# COM_R_BOARD.net
KiCad netlist of a schematic drawn in EAGLE
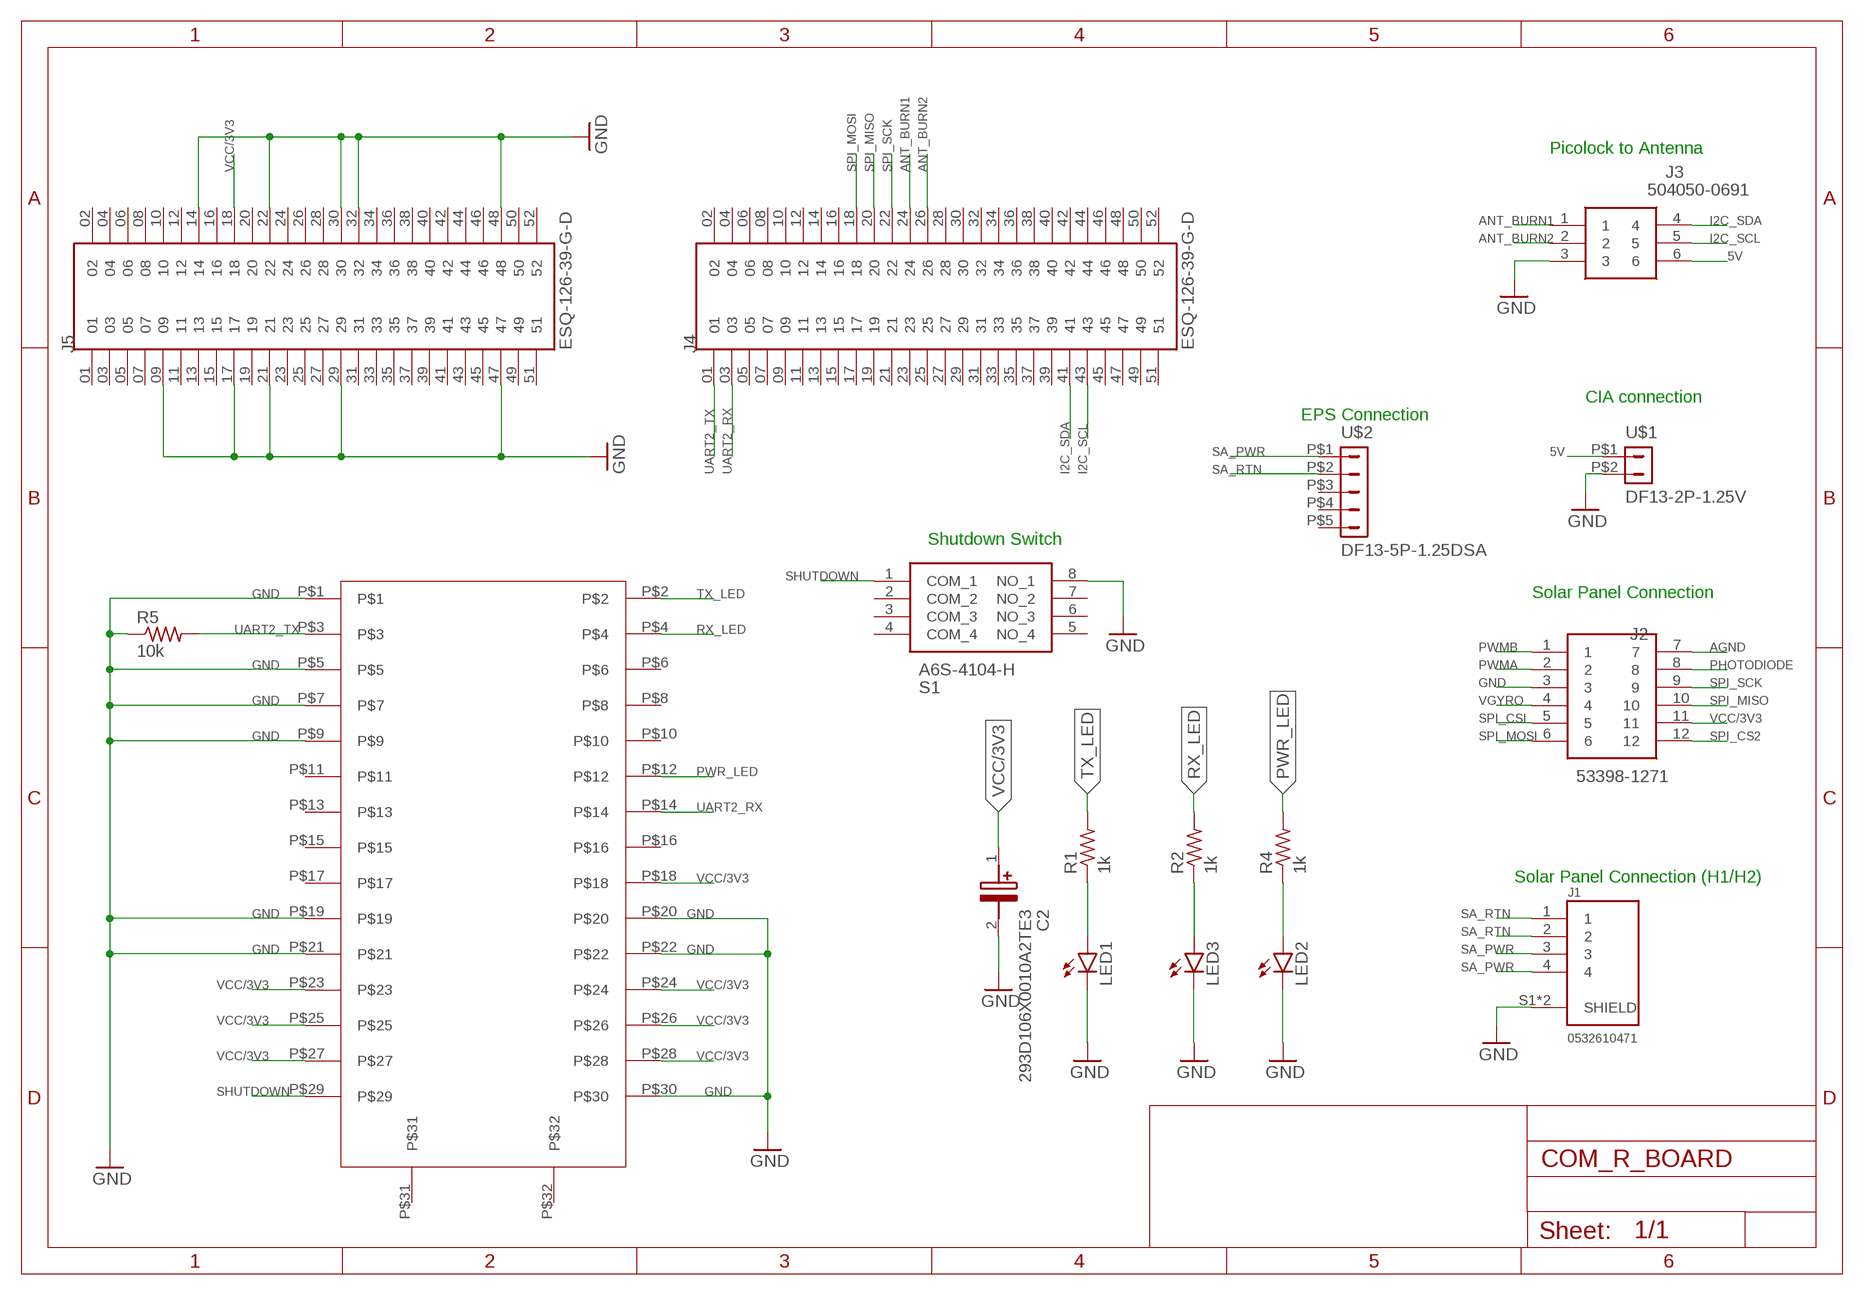
[diagram p0: schematic, sheet 1]

(export (version "E")
  (design (tool "Eeschema 10.0.6"))
  (components
    (comp (ref "C2")
      (value "293D106X0010A2TE3")
      (footprint "eagle-import:CAPPM3216X180N")
      (fields (field (name "MOUSER_PART_NUMBER") "74-293D106X0010A2TE3"))
      (libsource (lib "eagle-import") (part "293D106X0010A2TE3"))
    )
    (comp (ref "J1")
      (value "0532610471")
      (footprint "eagle-import:MOLEX_0532610471")
      (fields (field (name "MF") "Molex"))
      (libsource (lib "eagle-import") (part "0532610471"))
    )
    (comp (ref "J2")
      (value "53398-1271")
      (footprint "eagle-import:53398-1271")
      (fields (field (name "MOUSER_PART_NUMBER") "538-53398-1271"))
      (libsource (lib "eagle-import") (part "53398-1271"))
    )
    (comp (ref "J3")
      (value "504050-0691")
      (footprint "eagle-import:504050-0691_2")
      (fields (field (name "MOUSER_PART_NUMBER") "538-504050-0691"))
      (libsource (lib "eagle-import") (part "504050-0691"))
    )
    (comp (ref "J4")
      (value "ESQ-126-39-G-D")
      (footprint "eagle-import:SAMTEC_ESQ-126-39-G-D")
      (fields (field (name "MF") "Samtec"))
      (libsource (lib "eagle-import") (part "ESQ-126-39-G-D"))
    )
    (comp (ref "J5")
      (value "ESQ-126-39-G-D")
      (footprint "eagle-import:SAMTEC_ESQ-126-39-G-D")
      (fields (field (name "MF") "Samtec"))
      (libsource (lib "eagle-import") (part "ESQ-126-39-G-D"))
    )
    (comp (ref "LED1")
      (value "LEDCHIP-LED0805")
      (footprint "eagle-import:CHIP-LED0805")
      (libsource (lib "eagle-import") (part "LEDCHIP-LED0805"))
    )
    (comp (ref "LED2")
      (value "LEDCHIP-LED0805")
      (footprint "eagle-import:CHIP-LED0805")
      (libsource (lib "eagle-import") (part "LEDCHIP-LED0805"))
    )
    (comp (ref "LED3")
      (value "LEDCHIP-LED0805")
      (footprint "eagle-import:CHIP-LED0805")
      (libsource (lib "eagle-import") (part "LEDCHIP-LED0805"))
    )
    (comp (ref "R1")
      (value "1k")
      (footprint "eagle-import:M0805")
      (libsource (lib "eagle-import") (part "R-US_M0805"))
    )
    (comp (ref "R2")
      (value "1k")
      (footprint "eagle-import:M0805")
      (libsource (lib "eagle-import") (part "R-US_M0805"))
    )
    (comp (ref "R4")
      (value "1k")
      (footprint "eagle-import:M0805")
      (libsource (lib "eagle-import") (part "R-US_M0805"))
    )
    (comp (ref "R5")
      (value "10k")
      (footprint "eagle-import:WSC01_2")
      (libsource (lib "eagle-import") (part "R-US_WSC01/2"))
    )
    (comp (ref "S1")
      (value "A6S-4104-H")
      (footprint "eagle-import:A6S4104H")
      (fields (field (name "MOUSER_PART_NUMBER") "653-A6S-4104-H"))
      (libsource (lib "eagle-import") (part "A6S-4104-H"))
    )
    (comp (ref "U$1")
      (value "DF13-2P-1.25V")
      (footprint "eagle-import:DF13C-2P-1.25V")
      (libsource (lib "eagle-import") (part "DF13-2P-1.25V"))
    )
    (comp (ref "U$2")
      (value "DF13-5P-1.25DSA")
      (footprint "eagle-import:DF13-5P-1.25DSA")
      (libsource (lib "eagle-import") (part "DF13-5P-1.25DSA"))
    )
    (comp (ref "U$3")
      (value "KYOCERA_5046_30PIN")
      (footprint "eagle-import:KYOCERA_5046_30PIN")
      (libsource (lib "eagle-import") (part "KYOCERA_5046_30PIN"))
    )
  )
  (nets
    (net (code "1") (name "/5V") (class "Default")
      (node (ref "J3") (pin "6") (pinfunction "6_6") (pintype "bidirectional"))
      (node (ref "U$1") (pin "P$1") (pinfunction "1_P$1") (pintype "passive"))
    )
    (net (code "2") (name "/AGND") (class "Default")
      (node (ref "J2") (pin "7") (pinfunction "7_7") (pintype "bidirectional"))
    )
    (net (code "3") (name "/ANT_BURN1") (class "Default")
      (node (ref "J3") (pin "1") (pinfunction "1_1") (pintype "bidirectional"))
      (node (ref "J4") (pin "24") (pinfunction "24_24") (pintype "passive"))
    )
    (net (code "4") (name "/ANT_BURN2") (class "Default")
      (node (ref "J3") (pin "2") (pinfunction "2_2") (pintype "bidirectional"))
      (node (ref "J4") (pin "26") (pinfunction "26_26") (pintype "passive"))
    )
    (net (code "5") (name "/I2C_SCL") (class "Default")
      (node (ref "J3") (pin "5") (pinfunction "5_5") (pintype "bidirectional"))
      (node (ref "J4") (pin "43") (pinfunction "43_43") (pintype "passive"))
    )
    (net (code "6") (name "/I2C_SDA") (class "Default")
      (node (ref "J3") (pin "4") (pinfunction "4_4") (pintype "bidirectional"))
      (node (ref "J4") (pin "41") (pinfunction "41_41") (pintype "passive"))
    )
    (net (code "7") (name "/PHOTODIODE") (class "Default")
      (node (ref "J2") (pin "8") (pinfunction "8_8") (pintype "bidirectional"))
    )
    (net (code "8") (name "/PWMA") (class "Default")
      (node (ref "J2") (pin "2") (pinfunction "2_2") (pintype "bidirectional"))
    )
    (net (code "9") (name "/PWMB") (class "Default")
      (node (ref "J2") (pin "1") (pinfunction "1_1") (pintype "bidirectional"))
    )
    (net (code "10") (name "/SA_PWR") (class "Default")
      (node (ref "J1") (pin "3") (pinfunction "3_3") (pintype "passive"))
      (node (ref "J1") (pin "4") (pinfunction "4_4") (pintype "passive"))
      (node (ref "U$2") (pin "P$1") (pinfunction "1_P$1") (pintype "passive"))
    )
    (net (code "11") (name "/SA_RTN") (class "Default")
      (node (ref "J1") (pin "1") (pinfunction "1_1") (pintype "passive"))
      (node (ref "J1") (pin "2") (pinfunction "2_2") (pintype "passive"))
      (node (ref "U$2") (pin "P$2") (pinfunction "2_P$2") (pintype "passive"))
    )
    (net (code "12") (name "/SHUTDOWN") (class "Default")
      (node (ref "S1") (pin "1") (pinfunction "COM_1_1") (pintype "bidirectional"))
      (node (ref "U$3") (pin "P$29") (pinfunction "P$29_P$29") (pintype "bidirectional"))
    )
    (net (code "13") (name "/SPI_CS2") (class "Default")
      (node (ref "J2") (pin "12") (pinfunction "12_12") (pintype "bidirectional"))
    )
    (net (code "14") (name "/SPI_CSI") (class "Default")
      (node (ref "J2") (pin "5") (pinfunction "5_5") (pintype "bidirectional"))
    )
    (net (code "15") (name "/SPI_MISO") (class "Default")
      (node (ref "J2") (pin "10") (pinfunction "10_10") (pintype "bidirectional"))
      (node (ref "J4") (pin "20") (pinfunction "20_20") (pintype "passive"))
    )
    (net (code "16") (name "/SPI_MOSI") (class "Default")
      (node (ref "J2") (pin "6") (pinfunction "6_6") (pintype "bidirectional"))
      (node (ref "J4") (pin "18") (pinfunction "18_18") (pintype "passive"))
    )
    (net (code "17") (name "/SPI_SCK") (class "Default")
      (node (ref "J2") (pin "9") (pinfunction "9_9") (pintype "bidirectional"))
      (node (ref "J4") (pin "22") (pinfunction "22_22") (pintype "passive"))
    )
    (net (code "18") (name "/UART2_RX") (class "Default")
      (node (ref "J4") (pin "03") (pinfunction "03_03") (pintype "passive"))
      (node (ref "U$3") (pin "P$14") (pinfunction "P$14_P$14") (pintype "bidirectional"))
    )
    (net (code "19") (name "/UART2_TX") (class "Default")
      (node (ref "J4") (pin "01") (pinfunction "01_01") (pintype "passive"))
      (node (ref "R5") (pin "2") (pinfunction "2_2") (pintype "passive"))
      (node (ref "U$3") (pin "P$3") (pinfunction "P$3_P$3") (pintype "bidirectional"))
    )
    (net (code "20") (name "/VGYRO") (class "Default")
      (node (ref "J2") (pin "4") (pinfunction "4_4") (pintype "bidirectional"))
    )
    (net (code "21") (name "GND") (class "Default")
      (node (ref "C2") (pin "2") (pinfunction "-_2") (pintype "bidirectional"))
      (node (ref "J1") (pin "S1") (pinfunction "SHIELD_S1") (pintype "passive"))
      (node (ref "J1") (pin "S2") (pinfunction "SHIELD_S2") (pintype "passive"))
      (node (ref "J2") (pin "3") (pinfunction "3_3") (pintype "bidirectional"))
      (node (ref "J3") (pin "3") (pinfunction "3_3") (pintype "bidirectional"))
      (node (ref "J5") (pin "09") (pinfunction "09_09") (pintype "passive"))
      (node (ref "J5") (pin "14") (pinfunction "14_14") (pintype "passive"))
      (node (ref "J5") (pin "17") (pinfunction "17_17") (pintype "passive"))
      (node (ref "J5") (pin "21") (pinfunction "21_21") (pintype "passive"))
      (node (ref "J5") (pin "22") (pinfunction "22_22") (pintype "passive"))
      (node (ref "J5") (pin "29") (pinfunction "29_29") (pintype "passive"))
      (node (ref "J5") (pin "30") (pinfunction "30_30") (pintype "passive"))
      (node (ref "J5") (pin "32") (pinfunction "32_32") (pintype "passive"))
      (node (ref "J5") (pin "47") (pinfunction "47_47") (pintype "passive"))
      (node (ref "J5") (pin "48") (pinfunction "48_48") (pintype "passive"))
      (node (ref "LED1") (pin "C") (pinfunction "C_C") (pintype "passive"))
      (node (ref "LED2") (pin "C") (pinfunction "C_C") (pintype "passive"))
      (node (ref "LED3") (pin "C") (pinfunction "C_C") (pintype "passive"))
      (node (ref "R5") (pin "1") (pinfunction "1_1") (pintype "passive"))
      (node (ref "S1") (pin "8") (pinfunction "NO_1_8") (pintype "bidirectional"))
      (node (ref "U$1") (pin "P$2") (pinfunction "2_P$2") (pintype "passive"))
      (node (ref "U$3") (pin "P$1") (pinfunction "P$1_P$1") (pintype "bidirectional"))
      (node (ref "U$3") (pin "P$19") (pinfunction "P$19_P$19") (pintype "bidirectional"))
      (node (ref "U$3") (pin "P$20") (pinfunction "P$20_P$20") (pintype "bidirectional"))
      (node (ref "U$3") (pin "P$21") (pinfunction "P$21_P$21") (pintype "bidirectional"))
      (node (ref "U$3") (pin "P$22") (pinfunction "P$22_P$22") (pintype "bidirectional"))
      (node (ref "U$3") (pin "P$30") (pinfunction "P$30_P$30") (pintype "bidirectional"))
      (node (ref "U$3") (pin "P$5") (pinfunction "P$5_P$5") (pintype "bidirectional"))
      (node (ref "U$3") (pin "P$7") (pinfunction "P$7_P$7") (pintype "bidirectional"))
      (node (ref "U$3") (pin "P$9") (pinfunction "P$9_P$9") (pintype "bidirectional"))
    )
    (net (code "22") (name "Net-(LED1-PadA)") (class "Default")
      (node (ref "LED1") (pin "A") (pinfunction "A_A") (pintype "passive"))
      (node (ref "R1") (pin "1") (pinfunction "1_1") (pintype "passive"))
    )
    (net (code "23") (name "Net-(LED2-PadA)") (class "Default")
      (node (ref "LED2") (pin "A") (pinfunction "A_A") (pintype "passive"))
      (node (ref "R4") (pin "1") (pinfunction "1_1") (pintype "passive"))
    )
    (net (code "24") (name "Net-(LED3-PadA)") (class "Default")
      (node (ref "LED3") (pin "A") (pinfunction "A_A") (pintype "passive"))
      (node (ref "R2") (pin "1") (pinfunction "1_1") (pintype "passive"))
    )
    (net (code "25") (name "PWR_LED") (class "Default")
      (node (ref "R4") (pin "2") (pinfunction "2_2") (pintype "passive"))
      (node (ref "U$3") (pin "P$12") (pinfunction "P$12_P$12") (pintype "bidirectional"))
    )
    (net (code "26") (name "RX_LED") (class "Default")
      (node (ref "R2") (pin "2") (pinfunction "2_2") (pintype "passive"))
      (node (ref "U$3") (pin "P$4") (pinfunction "P$4_P$4") (pintype "bidirectional"))
    )
    (net (code "27") (name "TX_LED") (class "Default")
      (node (ref "R1") (pin "2") (pinfunction "2_2") (pintype "passive"))
      (node (ref "U$3") (pin "P$2") (pinfunction "P$2_P$2") (pintype "bidirectional"))
    )
    (net (code "28") (name "VCC{slash}3V3") (class "Default")
      (node (ref "C2") (pin "1") (pinfunction "+_1") (pintype "bidirectional"))
      (node (ref "J2") (pin "11") (pinfunction "11_11") (pintype "bidirectional"))
      (node (ref "J5") (pin "18") (pinfunction "18_18") (pintype "passive"))
      (node (ref "U$3") (pin "P$18") (pinfunction "P$18_P$18") (pintype "bidirectional"))
      (node (ref "U$3") (pin "P$23") (pinfunction "P$23_P$23") (pintype "bidirectional"))
      (node (ref "U$3") (pin "P$24") (pinfunction "P$24_P$24") (pintype "bidirectional"))
      (node (ref "U$3") (pin "P$25") (pinfunction "P$25_P$25") (pintype "bidirectional"))
      (node (ref "U$3") (pin "P$26") (pinfunction "P$26_P$26") (pintype "bidirectional"))
      (node (ref "U$3") (pin "P$27") (pinfunction "P$27_P$27") (pintype "bidirectional"))
      (node (ref "U$3") (pin "P$28") (pinfunction "P$28_P$28") (pintype "bidirectional"))
    )
    (net (code "29") (name "unconnected-(J4-Pad02)") (class "Default")
      (node (ref "J4") (pin "02") (pinfunction "02_02") (pintype "passive"))
    )
    (net (code "30") (name "unconnected-(J4-Pad04)") (class "Default")
      (node (ref "J4") (pin "04") (pinfunction "04_04") (pintype "passive"))
    )
    (net (code "31") (name "unconnected-(J4-Pad05)") (class "Default")
      (node (ref "J4") (pin "05") (pinfunction "05_05") (pintype "passive"))
    )
    (net (code "32") (name "unconnected-(J4-Pad06)") (class "Default")
      (node (ref "J4") (pin "06") (pinfunction "06_06") (pintype "passive"))
    )
    (net (code "33") (name "unconnected-(J4-Pad07)") (class "Default")
      (node (ref "J4") (pin "07") (pinfunction "07_07") (pintype "passive"))
    )
    (net (code "34") (name "unconnected-(J4-Pad08)") (class "Default")
      (node (ref "J4") (pin "08") (pinfunction "08_08") (pintype "passive"))
    )
    (net (code "35") (name "unconnected-(J4-Pad09)") (class "Default")
      (node (ref "J4") (pin "09") (pinfunction "09_09") (pintype "passive"))
    )
    (net (code "36") (name "unconnected-(J4-Pad10)") (class "Default")
      (node (ref "J4") (pin "10") (pinfunction "10_10") (pintype "passive"))
    )
    (net (code "37") (name "unconnected-(J4-Pad11)") (class "Default")
      (node (ref "J4") (pin "11") (pinfunction "11_11") (pintype "passive"))
    )
    (net (code "38") (name "unconnected-(J4-Pad12)") (class "Default")
      (node (ref "J4") (pin "12") (pinfunction "12_12") (pintype "passive"))
    )
    (net (code "39") (name "unconnected-(J4-Pad13)") (class "Default")
      (node (ref "J4") (pin "13") (pinfunction "13_13") (pintype "passive"))
    )
    (net (code "40") (name "unconnected-(J4-Pad14)") (class "Default")
      (node (ref "J4") (pin "14") (pinfunction "14_14") (pintype "passive"))
    )
    (net (code "41") (name "unconnected-(J4-Pad15)") (class "Default")
      (node (ref "J4") (pin "15") (pinfunction "15_15") (pintype "passive"))
    )
    (net (code "42") (name "unconnected-(J4-Pad16)") (class "Default")
      (node (ref "J4") (pin "16") (pinfunction "16_16") (pintype "passive"))
    )
    (net (code "43") (name "unconnected-(J4-Pad17)") (class "Default")
      (node (ref "J4") (pin "17") (pinfunction "17_17") (pintype "passive"))
    )
    (net (code "44") (name "unconnected-(J4-Pad19)") (class "Default")
      (node (ref "J4") (pin "19") (pinfunction "19_19") (pintype "passive"))
    )
    (net (code "45") (name "unconnected-(J4-Pad21)") (class "Default")
      (node (ref "J4") (pin "21") (pinfunction "21_21") (pintype "passive"))
    )
    (net (code "46") (name "unconnected-(J4-Pad23)") (class "Default")
      (node (ref "J4") (pin "23") (pinfunction "23_23") (pintype "passive"))
    )
    (net (code "47") (name "unconnected-(J4-Pad25)") (class "Default")
      (node (ref "J4") (pin "25") (pinfunction "25_25") (pintype "passive"))
    )
    (net (code "48") (name "unconnected-(J4-Pad27)") (class "Default")
      (node (ref "J4") (pin "27") (pinfunction "27_27") (pintype "passive"))
    )
    (net (code "49") (name "unconnected-(J4-Pad28)") (class "Default")
      (node (ref "J4") (pin "28") (pinfunction "28_28") (pintype "passive"))
    )
    (net (code "50") (name "unconnected-(J4-Pad29)") (class "Default")
      (node (ref "J4") (pin "29") (pinfunction "29_29") (pintype "passive"))
    )
    (net (code "51") (name "unconnected-(J4-Pad30)") (class "Default")
      (node (ref "J4") (pin "30") (pinfunction "30_30") (pintype "passive"))
    )
    (net (code "52") (name "unconnected-(J4-Pad31)") (class "Default")
      (node (ref "J4") (pin "31") (pinfunction "31_31") (pintype "passive"))
    )
    (net (code "53") (name "unconnected-(J4-Pad32)") (class "Default")
      (node (ref "J4") (pin "32") (pinfunction "32_32") (pintype "passive"))
    )
    (net (code "54") (name "unconnected-(J4-Pad33)") (class "Default")
      (node (ref "J4") (pin "33") (pinfunction "33_33") (pintype "passive"))
    )
    (net (code "55") (name "unconnected-(J4-Pad34)") (class "Default")
      (node (ref "J4") (pin "34") (pinfunction "34_34") (pintype "passive"))
    )
    (net (code "56") (name "unconnected-(J4-Pad35)") (class "Default")
      (node (ref "J4") (pin "35") (pinfunction "35_35") (pintype "passive"))
    )
    (net (code "57") (name "unconnected-(J4-Pad36)") (class "Default")
      (node (ref "J4") (pin "36") (pinfunction "36_36") (pintype "passive"))
    )
    (net (code "58") (name "unconnected-(J4-Pad37)") (class "Default")
      (node (ref "J4") (pin "37") (pinfunction "37_37") (pintype "passive"))
    )
    (net (code "59") (name "unconnected-(J4-Pad38)") (class "Default")
      (node (ref "J4") (pin "38") (pinfunction "38_38") (pintype "passive"))
    )
    (net (code "60") (name "unconnected-(J4-Pad39)") (class "Default")
      (node (ref "J4") (pin "39") (pinfunction "39_39") (pintype "passive"))
    )
    (net (code "61") (name "unconnected-(J4-Pad40)") (class "Default")
      (node (ref "J4") (pin "40") (pinfunction "40_40") (pintype "passive"))
    )
    (net (code "62") (name "unconnected-(J4-Pad42)") (class "Default")
      (node (ref "J4") (pin "42") (pinfunction "42_42") (pintype "passive"))
    )
    (net (code "63") (name "unconnected-(J4-Pad44)") (class "Default")
      (node (ref "J4") (pin "44") (pinfunction "44_44") (pintype "passive"))
    )
    (net (code "64") (name "unconnected-(J4-Pad45)") (class "Default")
      (node (ref "J4") (pin "45") (pinfunction "45_45") (pintype "passive"))
    )
    (net (code "65") (name "unconnected-(J4-Pad46)") (class "Default")
      (node (ref "J4") (pin "46") (pinfunction "46_46") (pintype "passive"))
    )
    (net (code "66") (name "unconnected-(J4-Pad47)") (class "Default")
      (node (ref "J4") (pin "47") (pinfunction "47_47") (pintype "passive"))
    )
    (net (code "67") (name "unconnected-(J4-Pad48)") (class "Default")
      (node (ref "J4") (pin "48") (pinfunction "48_48") (pintype "passive"))
    )
    (net (code "68") (name "unconnected-(J4-Pad49)") (class "Default")
      (node (ref "J4") (pin "49") (pinfunction "49_49") (pintype "passive"))
    )
    (net (code "69") (name "unconnected-(J4-Pad50)") (class "Default")
      (node (ref "J4") (pin "50") (pinfunction "50_50") (pintype "passive"))
    )
    (net (code "70") (name "unconnected-(J4-Pad51)") (class "Default")
      (node (ref "J4") (pin "51") (pinfunction "51_51") (pintype "passive"))
    )
    (net (code "71") (name "unconnected-(J4-Pad52)") (class "Default")
      (node (ref "J4") (pin "52") (pinfunction "52_52") (pintype "passive"))
    )
    (net (code "72") (name "unconnected-(J5-Pad01)") (class "Default")
      (node (ref "J5") (pin "01") (pinfunction "01_01") (pintype "passive"))
    )
    (net (code "73") (name "unconnected-(J5-Pad02)") (class "Default")
      (node (ref "J5") (pin "02") (pinfunction "02_02") (pintype "passive"))
    )
    (net (code "74") (name "unconnected-(J5-Pad03)") (class "Default")
      (node (ref "J5") (pin "03") (pinfunction "03_03") (pintype "passive"))
    )
    (net (code "75") (name "unconnected-(J5-Pad04)") (class "Default")
      (node (ref "J5") (pin "04") (pinfunction "04_04") (pintype "passive"))
    )
    (net (code "76") (name "unconnected-(J5-Pad05)") (class "Default")
      (node (ref "J5") (pin "05") (pinfunction "05_05") (pintype "passive"))
    )
    (net (code "77") (name "unconnected-(J5-Pad06)") (class "Default")
      (node (ref "J5") (pin "06") (pinfunction "06_06") (pintype "passive"))
    )
    (net (code "78") (name "unconnected-(J5-Pad07)") (class "Default")
      (node (ref "J5") (pin "07") (pinfunction "07_07") (pintype "passive"))
    )
    (net (code "79") (name "unconnected-(J5-Pad08)") (class "Default")
      (node (ref "J5") (pin "08") (pinfunction "08_08") (pintype "passive"))
    )
    (net (code "80") (name "unconnected-(J5-Pad10)") (class "Default")
      (node (ref "J5") (pin "10") (pinfunction "10_10") (pintype "passive"))
    )
    (net (code "81") (name "unconnected-(J5-Pad11)") (class "Default")
      (node (ref "J5") (pin "11") (pinfunction "11_11") (pintype "passive"))
    )
    (net (code "82") (name "unconnected-(J5-Pad12)") (class "Default")
      (node (ref "J5") (pin "12") (pinfunction "12_12") (pintype "passive"))
    )
    (net (code "83") (name "unconnected-(J5-Pad13)") (class "Default")
      (node (ref "J5") (pin "13") (pinfunction "13_13") (pintype "passive"))
    )
    (net (code "84") (name "unconnected-(J5-Pad15)") (class "Default")
      (node (ref "J5") (pin "15") (pinfunction "15_15") (pintype "passive"))
    )
    (net (code "85") (name "unconnected-(J5-Pad16)") (class "Default")
      (node (ref "J5") (pin "16") (pinfunction "16_16") (pintype "passive"))
    )
    (net (code "86") (name "unconnected-(J5-Pad19)") (class "Default")
      (node (ref "J5") (pin "19") (pinfunction "19_19") (pintype "passive"))
    )
    (net (code "87") (name "unconnected-(J5-Pad20)") (class "Default")
      (node (ref "J5") (pin "20") (pinfunction "20_20") (pintype "passive"))
    )
    (net (code "88") (name "unconnected-(J5-Pad23)") (class "Default")
      (node (ref "J5") (pin "23") (pinfunction "23_23") (pintype "passive"))
    )
    (net (code "89") (name "unconnected-(J5-Pad24)") (class "Default")
      (node (ref "J5") (pin "24") (pinfunction "24_24") (pintype "passive"))
    )
    (net (code "90") (name "unconnected-(J5-Pad25)") (class "Default")
      (node (ref "J5") (pin "25") (pinfunction "25_25") (pintype "passive"))
    )
    (net (code "91") (name "unconnected-(J5-Pad26)") (class "Default")
      (node (ref "J5") (pin "26") (pinfunction "26_26") (pintype "passive"))
    )
    (net (code "92") (name "unconnected-(J5-Pad27)") (class "Default")
      (node (ref "J5") (pin "27") (pinfunction "27_27") (pintype "passive"))
    )
    (net (code "93") (name "unconnected-(J5-Pad28)") (class "Default")
      (node (ref "J5") (pin "28") (pinfunction "28_28") (pintype "passive"))
    )
    (net (code "94") (name "unconnected-(J5-Pad31)") (class "Default")
      (node (ref "J5") (pin "31") (pinfunction "31_31") (pintype "passive"))
    )
    (net (code "95") (name "unconnected-(J5-Pad33)") (class "Default")
      (node (ref "J5") (pin "33") (pinfunction "33_33") (pintype "passive"))
    )
    (net (code "96") (name "unconnected-(J5-Pad34)") (class "Default")
      (node (ref "J5") (pin "34") (pinfunction "34_34") (pintype "passive"))
    )
    (net (code "97") (name "unconnected-(J5-Pad35)") (class "Default")
      (node (ref "J5") (pin "35") (pinfunction "35_35") (pintype "passive"))
    )
    (net (code "98") (name "unconnected-(J5-Pad36)") (class "Default")
      (node (ref "J5") (pin "36") (pinfunction "36_36") (pintype "passive"))
    )
    (net (code "99") (name "unconnected-(J5-Pad37)") (class "Default")
      (node (ref "J5") (pin "37") (pinfunction "37_37") (pintype "passive"))
    )
    (net (code "100") (name "unconnected-(J5-Pad38)") (class "Default")
      (node (ref "J5") (pin "38") (pinfunction "38_38") (pintype "passive"))
    )
    (net (code "101") (name "unconnected-(J5-Pad39)") (class "Default")
      (node (ref "J5") (pin "39") (pinfunction "39_39") (pintype "passive"))
    )
    (net (code "102") (name "unconnected-(J5-Pad40)") (class "Default")
      (node (ref "J5") (pin "40") (pinfunction "40_40") (pintype "passive"))
    )
    (net (code "103") (name "unconnected-(J5-Pad41)") (class "Default")
      (node (ref "J5") (pin "41") (pinfunction "41_41") (pintype "passive"))
    )
    (net (code "104") (name "unconnected-(J5-Pad42)") (class "Default")
      (node (ref "J5") (pin "42") (pinfunction "42_42") (pintype "passive"))
    )
    (net (code "105") (name "unconnected-(J5-Pad43)") (class "Default")
      (node (ref "J5") (pin "43") (pinfunction "43_43") (pintype "passive"))
    )
    (net (code "106") (name "unconnected-(J5-Pad44)") (class "Default")
      (node (ref "J5") (pin "44") (pinfunction "44_44") (pintype "passive"))
    )
    (net (code "107") (name "unconnected-(J5-Pad45)") (class "Default")
      (node (ref "J5") (pin "45") (pinfunction "45_45") (pintype "passive"))
    )
    (net (code "108") (name "unconnected-(J5-Pad46)") (class "Default")
      (node (ref "J5") (pin "46") (pinfunction "46_46") (pintype "passive"))
    )
    (net (code "109") (name "unconnected-(J5-Pad49)") (class "Default")
      (node (ref "J5") (pin "49") (pinfunction "49_49") (pintype "passive"))
    )
    (net (code "110") (name "unconnected-(J5-Pad50)") (class "Default")
      (node (ref "J5") (pin "50") (pinfunction "50_50") (pintype "passive"))
    )
    (net (code "111") (name "unconnected-(J5-Pad51)") (class "Default")
      (node (ref "J5") (pin "51") (pinfunction "51_51") (pintype "passive"))
    )
    (net (code "112") (name "unconnected-(J5-Pad52)") (class "Default")
      (node (ref "J5") (pin "52") (pinfunction "52_52") (pintype "passive"))
    )
    (net (code "113") (name "unconnected-(S1-COM_2-Pad2)") (class "Default")
      (node (ref "S1") (pin "2") (pinfunction "COM_2_2") (pintype "bidirectional"))
    )
    (net (code "114") (name "unconnected-(S1-COM_3-Pad3)") (class "Default")
      (node (ref "S1") (pin "3") (pinfunction "COM_3_3") (pintype "bidirectional"))
    )
    (net (code "115") (name "unconnected-(S1-COM_4-Pad4)") (class "Default")
      (node (ref "S1") (pin "4") (pinfunction "COM_4_4") (pintype "bidirectional"))
    )
    (net (code "116") (name "unconnected-(S1-NO_2-Pad7)") (class "Default")
      (node (ref "S1") (pin "7") (pinfunction "NO_2_7") (pintype "bidirectional"))
    )
    (net (code "117") (name "unconnected-(S1-NO_3-Pad6)") (class "Default")
      (node (ref "S1") (pin "6") (pinfunction "NO_3_6") (pintype "bidirectional"))
    )
    (net (code "118") (name "unconnected-(S1-NO_4-Pad5)") (class "Default")
      (node (ref "S1") (pin "5") (pinfunction "NO_4_5") (pintype "bidirectional"))
    )
    (net (code "119") (name "unconnected-(U$2-3-PadP$3)") (class "Default")
      (node (ref "U$2") (pin "P$3") (pinfunction "3_P$3") (pintype "passive"))
    )
    (net (code "120") (name "unconnected-(U$2-4-PadP$4)") (class "Default")
      (node (ref "U$2") (pin "P$4") (pinfunction "4_P$4") (pintype "passive"))
    )
    (net (code "121") (name "unconnected-(U$2-5-PadP$5)") (class "Default")
      (node (ref "U$2") (pin "P$5") (pinfunction "5_P$5") (pintype "passive"))
    )
    (net (code "122") (name "unconnected-(U$3-PadP$6)") (class "Default")
      (node (ref "U$3") (pin "P$6") (pinfunction "P$6_P$6") (pintype "bidirectional"))
    )
    (net (code "123") (name "unconnected-(U$3-PadP$8)") (class "Default")
      (node (ref "U$3") (pin "P$8") (pinfunction "P$8_P$8") (pintype "bidirectional"))
    )
    (net (code "124") (name "unconnected-(U$3-PadP$10)") (class "Default")
      (node (ref "U$3") (pin "P$10") (pinfunction "P$10_P$10") (pintype "bidirectional"))
    )
    (net (code "125") (name "unconnected-(U$3-PadP$11)") (class "Default")
      (node (ref "U$3") (pin "P$11") (pinfunction "P$11_P$11") (pintype "bidirectional"))
    )
    (net (code "126") (name "unconnected-(U$3-PadP$13)") (class "Default")
      (node (ref "U$3") (pin "P$13") (pinfunction "P$13_P$13") (pintype "bidirectional"))
    )
    (net (code "127") (name "unconnected-(U$3-PadP$15)") (class "Default")
      (node (ref "U$3") (pin "P$15") (pinfunction "P$15_P$15") (pintype "bidirectional"))
    )
    (net (code "128") (name "unconnected-(U$3-PadP$16)") (class "Default")
      (node (ref "U$3") (pin "P$16") (pinfunction "P$16_P$16") (pintype "bidirectional"))
    )
    (net (code "129") (name "unconnected-(U$3-PadP$17)") (class "Default")
      (node (ref "U$3") (pin "P$17") (pinfunction "P$17_P$17") (pintype "bidirectional"))
    )
    (net (code "130") (name "unconnected-(U$3-PadP$31)") (class "Default")
      (node (ref "U$3") (pin "P$31") (pinfunction "P$31_P$31") (pintype "bidirectional"))
    )
    (net (code "131") (name "unconnected-(U$3-PadP$32)") (class "Default")
      (node (ref "U$3") (pin "P$32") (pinfunction "P$32_P$32") (pintype "bidirectional"))
    )
  )
)
